# P04_Power.net
KiCad netlist of a schematic drawn in Altium Designer
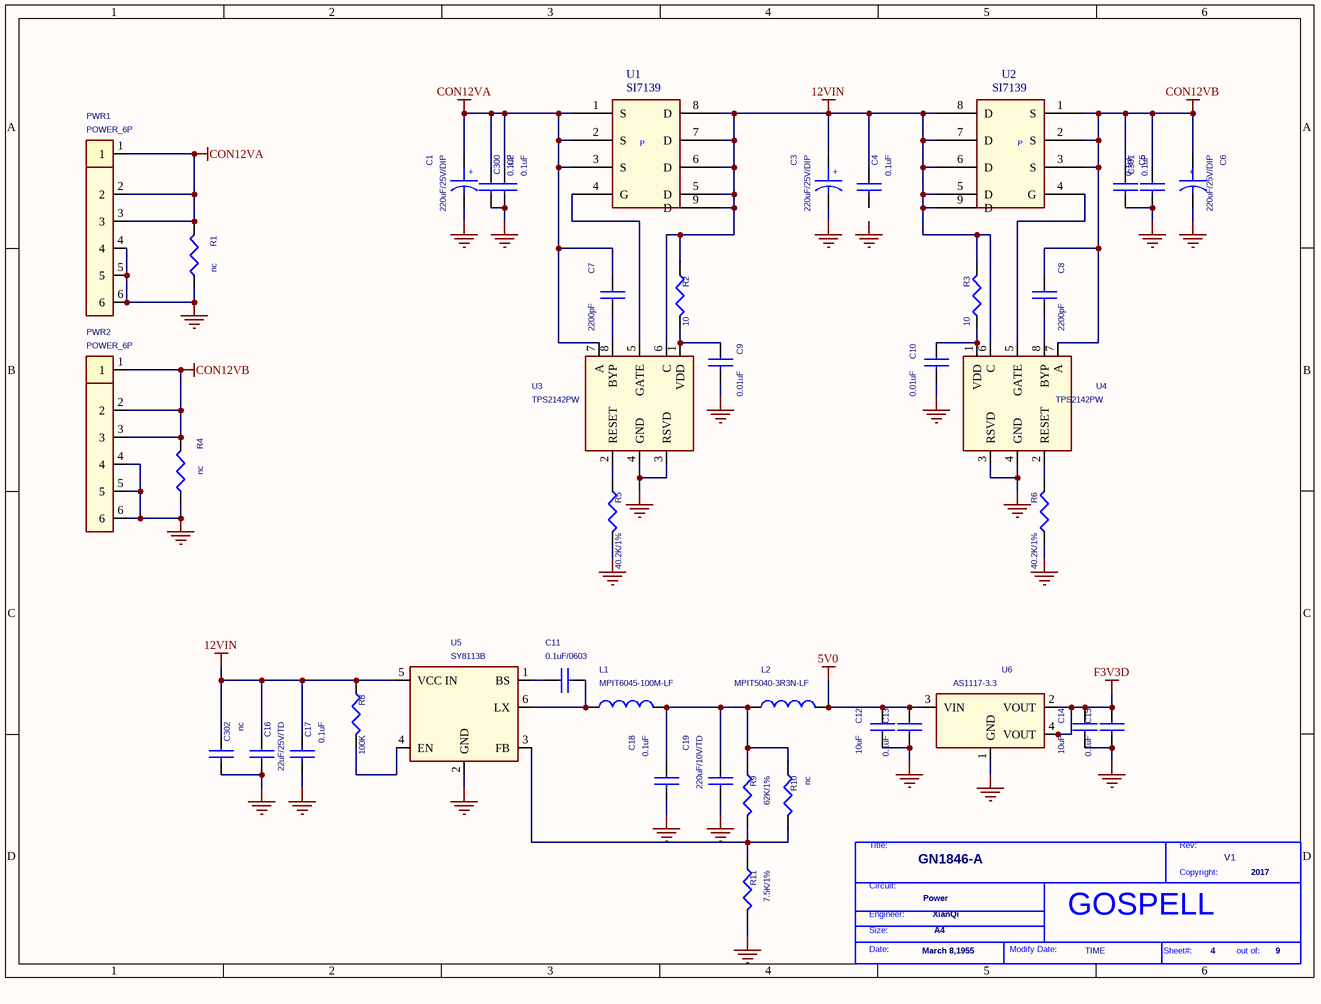
[diagram p0: P04 Power.SchDoc]

(export (version "E")
  (design (tool "Eeschema 10.0.6"))
  (components
    (comp (ref "C1") (value "220uF/25V/DIP") (libsource (lib "") (part "CAP POL_1")))
    (comp (ref "C2") (value "0.1uF") (libsource (lib "*") (part "CAP NP")))
    (comp (ref "C3") (value "220uF/25V/DIP") (libsource (lib "") (part "CAP POL_1")))
    (comp (ref "C4") (value "0.1uF") (libsource (lib "*") (part "CAP NP")))
    (comp (ref "C5") (value "0.1uF") (libsource (lib "*") (part "CAP NP")))
    (comp (ref "C6") (value "220uF/25V/DIP") (libsource (lib "*") (part "CAP POL")))
    (comp (ref "C7") (value "2200pF") (libsource (lib "*") (part "CAP NP")))
    (comp (ref "C8") (value "2200pF") (libsource (lib "*") (part "CAP NP")))
    (comp (ref "C9") (value "0.01uF") (libsource (lib "*") (part "CAP NP")))
    (comp (ref "C10") (value "0.01uF") (libsource (lib "*") (part "CAP NP")))
    (comp (ref "C11") (value "0.1uF/0603") (libsource (lib "*") (part "CAP NP")))
    (comp (ref "C12") (value "10uF") (libsource (lib "*") (part "CAP NP_Dup1")))
    (comp (ref "C13") (value "0.1uF") (libsource (lib "*") (part "CAP NP_Dup1")))
    (comp (ref "C14") (value "10uF") (libsource (lib "*") (part "CAP NP_Dup1")))
    (comp (ref "C15") (value "0.1uF") (libsource (lib "*") (part "CAP NP_Dup1")))
    (comp (ref "C16") (value "22uF/25V/TD") (libsource (lib "*") (part "CAP NP")))
    (comp (ref "C17") (value "0.1uF") (libsource (lib "*") (part "CAP NP")))
    (comp (ref "C18") (value "0.1uF") (libsource (lib "*") (part "CAP NP")))
    (comp (ref "C19") (value "220uF/10V/TD") (libsource (lib "*") (part "CAP NP")))
    (comp (ref "C300") (value "0.1uF") (libsource (lib "*") (part "CAP NP")))
    (comp (ref "C301") (value "0.1uF") (libsource (lib "*") (part "CAP NP")))
    (comp (ref "C302") (value "nc") (libsource (lib "*") (part "CAP NP")))
    (comp (ref "L1") (value "MPIT6045-100M-LF") (libsource (lib "*") (part "CHOKE TORROID_0")))
    (comp (ref "L2") (value "MPIT5040-3R3N-LF") (libsource (lib "*") (part "CHOKE TORROID_0")))
    (comp (ref "PWR1")
      (value "POWER_6P")
      (footprint "TJC2-6")
      (libsource (lib "GN-1846-A-V1") (part "POWER_4P"))
    )
    (comp (ref "PWR2")
      (value "POWER_6P")
      (footprint "TJC2-6")
      (libsource (lib "GN-1846-A-V1") (part "POWER_4P"))
    )
    (comp (ref "R1") (value "nc") (libsource (lib "*") (part "R")))
    (comp (ref "R2") (value "10") (libsource (lib "*") (part "R")))
    (comp (ref "R3") (value "10") (libsource (lib "*") (part "R")))
    (comp (ref "R4") (value "nc") (libsource (lib "*") (part "R")))
    (comp (ref "R5") (value "40.2K/1%") (libsource (lib "*") (part "R")))
    (comp (ref "R6") (value "40.2K/1%") (libsource (lib "*") (part "R")))
    (comp (ref "R8") (value "100K") (libsource (lib "*") (part "R")))
    (comp (ref "R9") (value "62K/1%") (libsource (lib "*") (part "R")))
    (comp (ref "R10") (value "nc") (libsource (lib "*") (part "R")))
    (comp (ref "R11") (value "7.5K/1%") (libsource (lib "*") (part "R")))
    (comp (ref "U1")
      (value "SI7139")
      (footprint "PowerPAKSO8")
      (libsource (lib "GN-1846-A-V1_Library") (part "SI7139"))
    )
    (comp (ref "U2") (value "SI7139") (footprint "PowerPAKSO8") (libsource (lib "") (part "SI7139_1")))
    (comp (ref "U3") (value "TPS2142PW") (footprint "TSSOP-8") (libsource (lib "*") (part "TPS2142PW")))
    (comp (ref "U4") (value "TPS2142PW") (footprint "TSSOP-8") (libsource (lib "") (part "TPS2142PW_1")))
    (comp (ref "U5") (value "SY8113B") (footprint "SOT23_6_G") (libsource (lib "*") (part "SY8120")))
    (comp (ref "U6") (value "AS1117-3.3") (footprint "SOT223") (libsource (lib "*") (part "AS1117-X_0")))
  )
  (nets
    (net (code "1") (name "5V0") (class "Default")
      (node (ref "C12") (pin "1") (pinfunction "1_1") (pintype "passive"))
      (node (ref "C13") (pin "1") (pinfunction "1_1") (pintype "passive"))
      (node (ref "L2") (pin "2") (pinfunction "2_2") (pintype "passive"))
      (node (ref "U6") (pin "3") (pinfunction "VIN_3") (pintype "passive"))
    )
    (net (code "2") (name "12VIN") (class "Default")
      (node (ref "C16") (pin "1") (pinfunction "1_1") (pintype "passive"))
      (node (ref "C17") (pin "1") (pinfunction "1_1") (pintype "passive"))
      (node (ref "C3") (pin "1") (pinfunction "1_1") (pintype "passive"))
      (node (ref "C302") (pin "1") (pinfunction "1_1") (pintype "passive"))
      (node (ref "C4") (pin "1") (pinfunction "1_1") (pintype "passive"))
      (node (ref "R2") (pin "1") (pinfunction "1_1") (pintype "passive"))
      (node (ref "R3") (pin "1") (pinfunction "1_1") (pintype "passive"))
      (node (ref "R8") (pin "1") (pinfunction "1_1") (pintype "passive"))
      (node (ref "U1") (pin "5") (pinfunction "D_5") (pintype "passive"))
      (node (ref "U1") (pin "6") (pinfunction "D_6") (pintype "passive"))
      (node (ref "U1") (pin "7") (pinfunction "D_7") (pintype "passive"))
      (node (ref "U1") (pin "8") (pinfunction "D_8") (pintype "passive"))
      (node (ref "U1") (pin "9") (pinfunction "D_9") (pintype "passive"))
      (node (ref "U2") (pin "5") (pinfunction "D_5") (pintype "passive"))
      (node (ref "U2") (pin "6") (pinfunction "D_6") (pintype "passive"))
      (node (ref "U2") (pin "7") (pinfunction "D_7") (pintype "passive"))
      (node (ref "U2") (pin "8") (pinfunction "D_8") (pintype "passive"))
      (node (ref "U2") (pin "9") (pinfunction "D_9") (pintype "passive"))
      (node (ref "U3") (pin "6") (pinfunction "C_6") (pintype "passive"))
      (node (ref "U4") (pin "6") (pinfunction "C_6") (pintype "passive"))
      (node (ref "U5") (pin "5") (pinfunction "VCC_IN_5") (pintype "passive"))
    )
    (net (code "3") (name "CON12VA") (class "Default")
      (node (ref "C1") (pin "1") (pinfunction "1_1") (pintype "passive"))
      (node (ref "C2") (pin "1") (pinfunction "1_1") (pintype "passive"))
      (node (ref "C300") (pin "1") (pinfunction "1_1") (pintype "passive"))
      (node (ref "C7") (pin "1") (pinfunction "1_1") (pintype "passive"))
      (node (ref "PWR1") (pin "1") (pinfunction "1_1") (pintype "passive"))
      (node (ref "PWR1") (pin "2") (pinfunction "2_2") (pintype "passive"))
      (node (ref "PWR1") (pin "3") (pinfunction "3_3") (pintype "passive"))
      (node (ref "R1") (pin "1") (pinfunction "1_1") (pintype "passive"))
      (node (ref "U1") (pin "1") (pinfunction "S_1") (pintype "passive"))
      (node (ref "U1") (pin "2") (pinfunction "S_2") (pintype "passive"))
      (node (ref "U1") (pin "3") (pinfunction "S_3") (pintype "passive"))
      (node (ref "U3") (pin "7") (pinfunction "A_7") (pintype "passive"))
    )
    (net (code "4") (name "CON12VB") (class "Default")
      (node (ref "C301") (pin "1") (pinfunction "1_1") (pintype "passive"))
      (node (ref "C5") (pin "1") (pinfunction "1_1") (pintype "passive"))
      (node (ref "C6") (pin "1") (pinfunction "1_1") (pintype "passive"))
      (node (ref "C8") (pin "1") (pinfunction "1_1") (pintype "passive"))
      (node (ref "PWR2") (pin "1") (pinfunction "1_1") (pintype "passive"))
      (node (ref "PWR2") (pin "2") (pinfunction "2_2") (pintype "passive"))
      (node (ref "PWR2") (pin "3") (pinfunction "3_3") (pintype "passive"))
      (node (ref "R4") (pin "1") (pinfunction "1_1") (pintype "passive"))
      (node (ref "U2") (pin "1") (pinfunction "S_1") (pintype "passive"))
      (node (ref "U2") (pin "2") (pinfunction "S_2") (pintype "passive"))
      (node (ref "U2") (pin "3") (pinfunction "S_3") (pintype "passive"))
      (node (ref "U4") (pin "7") (pinfunction "A_7") (pintype "passive"))
    )
    (net (code "5") (name "F3V3D") (class "Default")
      (node (ref "C14") (pin "1") (pinfunction "1_1") (pintype "passive"))
      (node (ref "C15") (pin "1") (pinfunction "1_1") (pintype "passive"))
      (node (ref "U6") (pin "2") (pinfunction "VOUT_2") (pintype "passive"))
      (node (ref "U6") (pin "4") (pinfunction "VOUT_4") (pintype "passive"))
    )
    (net (code "6") (name "GND") (class "Default")
      (node (ref "C1") (pin "2") (pinfunction "2_2") (pintype "passive"))
      (node (ref "C10") (pin "2") (pinfunction "2_2") (pintype "passive"))
      (node (ref "C12") (pin "2") (pinfunction "2_2") (pintype "passive"))
      (node (ref "C13") (pin "2") (pinfunction "2_2") (pintype "passive"))
      (node (ref "C14") (pin "2") (pinfunction "2_2") (pintype "passive"))
      (node (ref "C15") (pin "2") (pinfunction "2_2") (pintype "passive"))
      (node (ref "C16") (pin "2") (pinfunction "2_2") (pintype "passive"))
      (node (ref "C17") (pin "2") (pinfunction "2_2") (pintype "passive"))
      (node (ref "C18") (pin "2") (pinfunction "2_2") (pintype "passive"))
      (node (ref "C19") (pin "2") (pinfunction "2_2") (pintype "passive"))
      (node (ref "C2") (pin "2") (pinfunction "2_2") (pintype "passive"))
      (node (ref "C3") (pin "2") (pinfunction "2_2") (pintype "passive"))
      (node (ref "C300") (pin "2") (pinfunction "2_2") (pintype "passive"))
      (node (ref "C301") (pin "2") (pinfunction "2_2") (pintype "passive"))
      (node (ref "C302") (pin "2") (pinfunction "2_2") (pintype "passive"))
      (node (ref "C5") (pin "2") (pinfunction "2_2") (pintype "passive"))
      (node (ref "C6") (pin "2") (pinfunction "2_2") (pintype "passive"))
      (node (ref "C9") (pin "2") (pinfunction "2_2") (pintype "passive"))
      (node (ref "PWR1") (pin "4") (pinfunction "4_4") (pintype "passive"))
      (node (ref "PWR1") (pin "5") (pinfunction "5_5") (pintype "passive"))
      (node (ref "PWR1") (pin "6") (pinfunction "6_6") (pintype "passive"))
      (node (ref "PWR2") (pin "4") (pinfunction "4_4") (pintype "passive"))
      (node (ref "PWR2") (pin "5") (pinfunction "5_5") (pintype "passive"))
      (node (ref "PWR2") (pin "6") (pinfunction "6_6") (pintype "passive"))
      (node (ref "R1") (pin "2") (pinfunction "2_2") (pintype "passive"))
      (node (ref "R11") (pin "2") (pinfunction "2_2") (pintype "passive"))
      (node (ref "R4") (pin "2") (pinfunction "2_2") (pintype "passive"))
      (node (ref "R5") (pin "2") (pinfunction "2_2") (pintype "passive"))
      (node (ref "R6") (pin "2") (pinfunction "2_2") (pintype "passive"))
      (node (ref "U3") (pin "3") (pinfunction "RSVD_3") (pintype "passive"))
      (node (ref "U3") (pin "4") (pinfunction "GND_4") (pintype "passive"))
      (node (ref "U4") (pin "3") (pinfunction "RSVD_3") (pintype "passive"))
      (node (ref "U4") (pin "4") (pinfunction "GND_4") (pintype "passive"))
      (node (ref "U5") (pin "2") (pinfunction "GND_2") (pintype "passive"))
      (node (ref "U6") (pin "1") (pinfunction "GND_1") (pintype "passive"))
    )
    (net (code "7") (name "Net-(C18-Pad1)") (class "Default")
      (node (ref "C18") (pin "1") (pinfunction "1_1") (pintype "passive"))
      (node (ref "C19") (pin "1") (pinfunction "1_1") (pintype "passive"))
      (node (ref "L1") (pin "2") (pinfunction "2_2") (pintype "passive"))
      (node (ref "L2") (pin "1") (pinfunction "1_1") (pintype "passive"))
      (node (ref "R10") (pin "1") (pinfunction "1_1") (pintype "passive"))
      (node (ref "R9") (pin "1") (pinfunction "1_1") (pintype "passive"))
    )
    (net (code "8") (name "Net-(U1-G)") (class "Default")
      (node (ref "U1") (pin "4") (pinfunction "G_4") (pintype "passive"))
      (node (ref "U3") (pin "5") (pinfunction "GATE_5") (pintype "passive"))
    )
    (net (code "9") (name "Net-(U2-G)") (class "Default")
      (node (ref "U2") (pin "4") (pinfunction "G_4") (pintype "passive"))
      (node (ref "U4") (pin "5") (pinfunction "GATE_5") (pintype "passive"))
    )
    (net (code "10") (name "Net-(U3-BYP)") (class "Default")
      (node (ref "C7") (pin "2") (pinfunction "2_2") (pintype "passive"))
      (node (ref "U3") (pin "8") (pinfunction "BYP_8") (pintype "passive"))
    )
    (net (code "11") (name "Net-(U3-RESET)") (class "Default")
      (node (ref "R5") (pin "1") (pinfunction "1_1") (pintype "passive"))
      (node (ref "U3") (pin "2") (pinfunction "RESET_2") (pintype "passive"))
    )
    (net (code "12") (name "Net-(U3-VDD)") (class "Default")
      (node (ref "C9") (pin "1") (pinfunction "1_1") (pintype "passive"))
      (node (ref "R2") (pin "2") (pinfunction "2_2") (pintype "passive"))
      (node (ref "U3") (pin "1") (pinfunction "VDD_1") (pintype "passive"))
    )
    (net (code "13") (name "Net-(U4-BYP)") (class "Default")
      (node (ref "C8") (pin "2") (pinfunction "2_2") (pintype "passive"))
      (node (ref "U4") (pin "8") (pinfunction "BYP_8") (pintype "passive"))
    )
    (net (code "14") (name "Net-(U4-RESET)") (class "Default")
      (node (ref "R6") (pin "1") (pinfunction "1_1") (pintype "passive"))
      (node (ref "U4") (pin "2") (pinfunction "RESET_2") (pintype "passive"))
    )
    (net (code "15") (name "Net-(U4-VDD)") (class "Default")
      (node (ref "C10") (pin "1") (pinfunction "1_1") (pintype "passive"))
      (node (ref "R3") (pin "2") (pinfunction "2_2") (pintype "passive"))
      (node (ref "U4") (pin "1") (pinfunction "VDD_1") (pintype "passive"))
    )
    (net (code "16") (name "Net-(U5-BS)") (class "Default")
      (node (ref "C11") (pin "1") (pinfunction "1_1") (pintype "passive"))
      (node (ref "U5") (pin "1") (pinfunction "BS_1") (pintype "passive"))
    )
    (net (code "17") (name "Net-(U5-EN)") (class "Default")
      (node (ref "R8") (pin "2") (pinfunction "2_2") (pintype "passive"))
      (node (ref "U5") (pin "4") (pinfunction "EN_4") (pintype "passive"))
    )
    (net (code "18") (name "Net-(U5-FB)") (class "Default")
      (node (ref "R10") (pin "2") (pinfunction "2_2") (pintype "passive"))
      (node (ref "R11") (pin "1") (pinfunction "1_1") (pintype "passive"))
      (node (ref "R9") (pin "2") (pinfunction "2_2") (pintype "passive"))
      (node (ref "U5") (pin "3") (pinfunction "FB_3") (pintype "passive"))
    )
    (net (code "19") (name "Net-(U5-LX)") (class "Default")
      (node (ref "C11") (pin "2") (pinfunction "2_2") (pintype "passive"))
      (node (ref "L1") (pin "1") (pinfunction "1_1") (pintype "passive"))
      (node (ref "U5") (pin "6") (pinfunction "LX_6") (pintype "passive"))
    )
    (net (code "20") (name "unconnected-(C4-Pad2)") (class "Default")
      (node (ref "C4") (pin "2") (pinfunction "2_2") (pintype "passive"))
    )
  )
)
